# 5_TPS7A49.net
KiCad netlist of a schematic drawn in Altium Designer
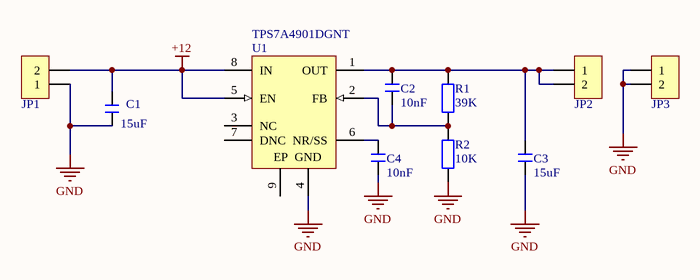
[diagram p0: 5_TPS7A49可调低压降稳压器.SchDoc]

(export (version "E")
  (design (tool "Eeschema 10.0.6"))
  (components
    (comp (ref "C1")
      (value "15uF")
      (footprint "C 0805_L")
      (description "贴片电容")
      (libsource (lib "01 - 电容-电阻-电感") (part "C"))
    )
    (comp (ref "C2")
      (value "10nF")
      (footprint "C 0805_L")
      (description "贴片电容")
      (libsource (lib "01 - 电容-电阻-电感") (part "C"))
    )
    (comp (ref "C3")
      (value "15uF")
      (footprint "C 0805_L")
      (description "贴片电容")
      (libsource (lib "01 - 电容-电阻-电感") (part "C"))
    )
    (comp (ref "C4")
      (value "10nF")
      (footprint "C 0805_L")
      (description "贴片电容")
      (libsource (lib "01 - 电容-电阻-电感") (part "C"))
    )
    (comp (ref "JP1")
      (value "HDR-1X2")
      (footprint "KF2EDGK5.08-WI-2P")
      (description "2P接插件")
      (libsource (lib "22 - 接插件-脚距5.08mm (200mil) ") (part "Header 2"))
    )
    (comp (ref "JP2")
      (value "HDR-1X2")
      (footprint "HDR2.54-WS-2P")
      (description "2P接插件")
      (libsource (lib "17 - 接插件-脚距2.54mm (100mil) ") (part "Header 2"))
    )
    (comp (ref "JP3")
      (value "HDR-1X2")
      (footprint "HDR2.54-WS-2P")
      (description "2P接插件")
      (libsource (lib "17 - 接插件-脚距2.54mm (100mil) ") (part "Header 2"))
    )
    (comp (ref "R1")
      (value "39K")
      (footprint "R 0805_L")
      (description "贴片电阻")
      (libsource (lib "01 - 电容-电阻-电感") (part "R"))
    )
    (comp (ref "R2")
      (value "10K")
      (footprint "R 0805_L")
      (description "贴片电阻")
      (libsource (lib "01 - 电容-电阻-电感") (part "R"))
    )
    (comp (ref "U1")
      (value "TPS7A4901DGNT")
      (footprint "DGN0008D_M")
      (fields (field (name "MANUFACTURER") "Texas Instruments"))
      (libsource (lib "Altium Content Vault") (part "TI-TPS7AXX01-YYDGN8-1760X1425TP"))
    )
  )
  (nets
    (net (code "1") (name "+12") (class "Default")
      (node (ref "C1") (pin "2") (pinfunction "2_2") (pintype "passive"))
      (node (ref "JP1") (pin "2") (pinfunction "2_2") (pintype "passive"))
      (node (ref "U1") (pin "5") (pinfunction "EN_5") (pintype "input"))
      (node (ref "U1") (pin "8") (pinfunction "IN_8") (pintype "power_in"))
    )
    (net (code "2") (name "GND") (class "Default")
      (node (ref "C1") (pin "1") (pinfunction "1_1") (pintype "passive"))
      (node (ref "C3") (pin "1") (pinfunction "1_1") (pintype "passive"))
      (node (ref "C4") (pin "1") (pinfunction "1_1") (pintype "passive"))
      (node (ref "JP1") (pin "1") (pinfunction "1_1") (pintype "passive"))
      (node (ref "JP3") (pin "1") (pinfunction "1_1") (pintype "passive"))
      (node (ref "JP3") (pin "2") (pinfunction "2_2") (pintype "passive"))
      (node (ref "R2") (pin "1") (pinfunction "1_1") (pintype "passive"))
      (node (ref "U1") (pin "4") (pinfunction "GND_4") (pintype "power_in"))
    )
    (net (code "3") (name "Net-(U1-FB)") (class "Default")
      (node (ref "C2") (pin "1") (pinfunction "1_1") (pintype "passive"))
      (node (ref "R1") (pin "1") (pinfunction "1_1") (pintype "passive"))
      (node (ref "R2") (pin "2") (pinfunction "2_2") (pintype "passive"))
      (node (ref "U1") (pin "2") (pinfunction "FB_2") (pintype "input"))
    )
    (net (code "4") (name "Net-(U1-NR{slash}SS)") (class "Default")
      (node (ref "C4") (pin "2") (pinfunction "2_2") (pintype "passive"))
      (node (ref "U1") (pin "6") (pinfunction "NR/SS_6") (pintype "passive"))
    )
    (net (code "5") (name "Net-(U1-OUT)") (class "Default")
      (node (ref "C2") (pin "2") (pinfunction "2_2") (pintype "passive"))
      (node (ref "C3") (pin "2") (pinfunction "2_2") (pintype "passive"))
      (node (ref "JP2") (pin "1") (pinfunction "1_1") (pintype "passive"))
      (node (ref "JP2") (pin "2") (pinfunction "2_2") (pintype "passive"))
      (node (ref "R1") (pin "2") (pinfunction "2_2") (pintype "passive"))
      (node (ref "U1") (pin "1") (pinfunction "OUT_1") (pintype "power_in"))
    )
    (net (code "6") (name "unconnected-(U1-DNC-Pad7)") (class "Default")
      (node (ref "U1") (pin "7") (pinfunction "DNC_7") (pintype "passive"))
    )
    (net (code "7") (name "unconnected-(U1-EP-Pad9)") (class "Default")
      (node (ref "U1") (pin "9") (pinfunction "EP_9") (pintype "power_in"))
    )
    (net (code "8") (name "unconnected-(U1-NC-Pad3)") (class "Default")
      (node (ref "U1") (pin "3") (pinfunction "NC_3") (pintype "passive"))
    )
  )
)
